# 72x8_control.net
KiCad netlist of a schematic drawn in EAGLE
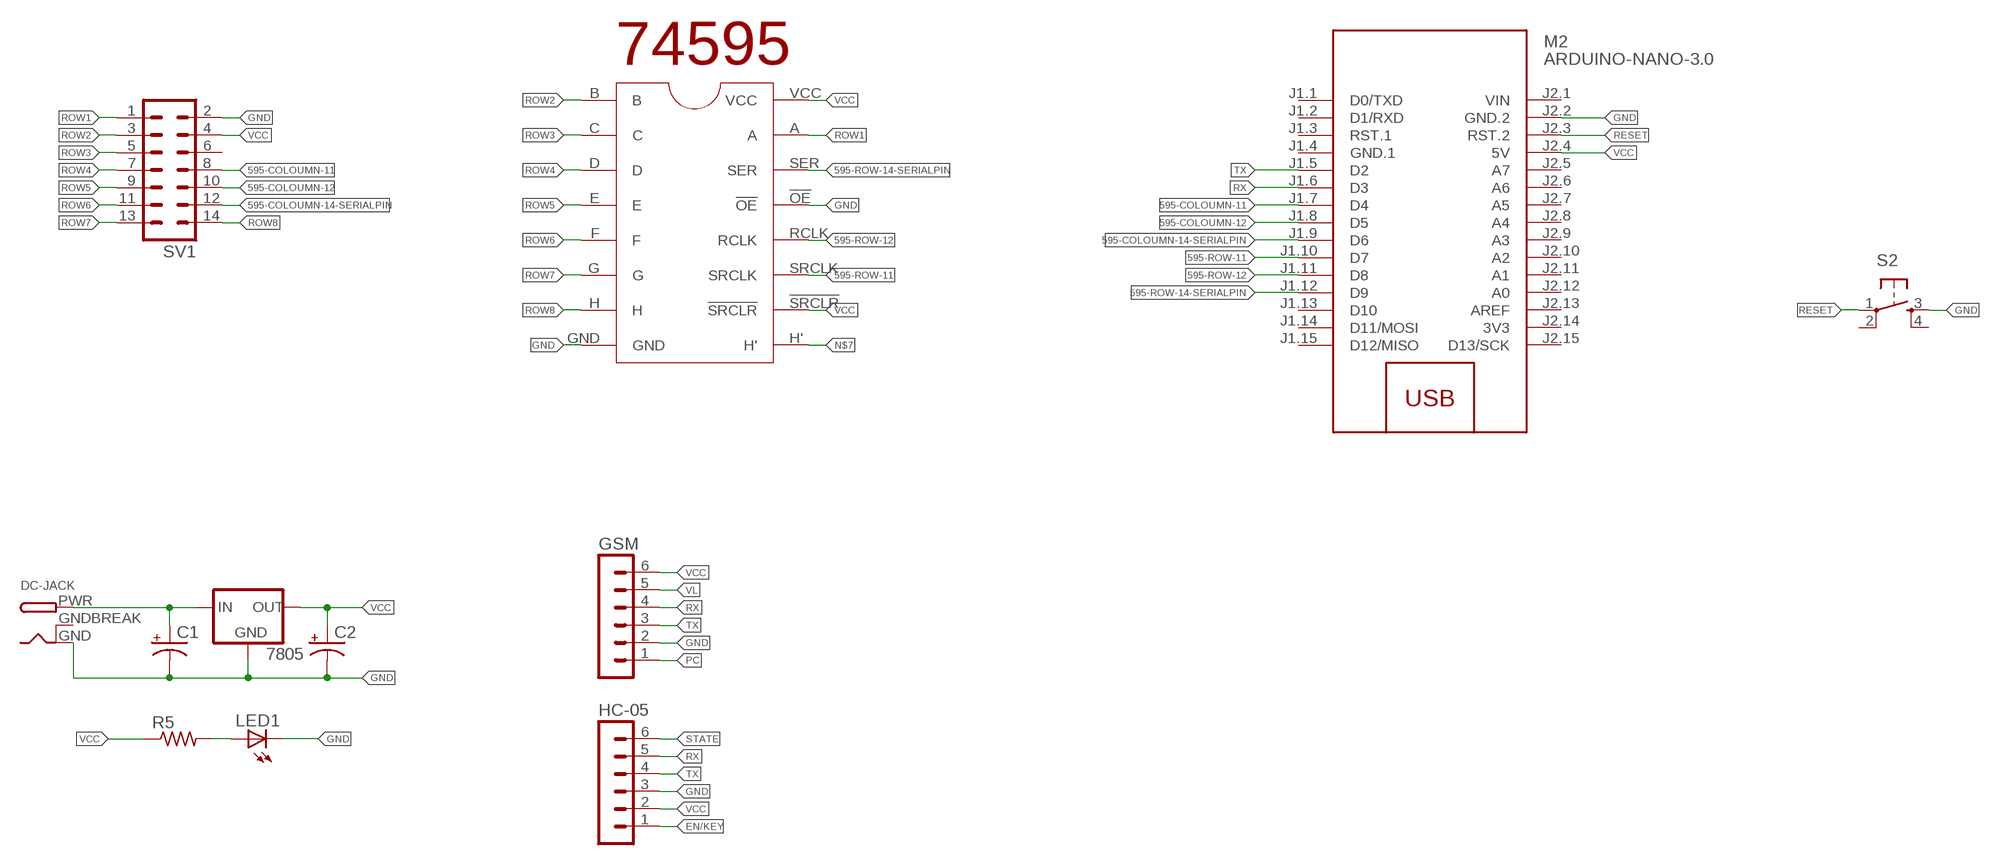
[diagram p0: schematic, sheet 1]

(export (version "E")
  (design (tool "Eeschema 10.0.6"))
  (components
    (comp (ref "1")
      (value "74595")
      (footprint "eagle-import:DIL16")
      (libsource (lib "eagle-import") (part "74595"))
    )
    (comp (ref "7805")
      (value "78XX-TO3")
      (footprint "eagle-import:TO3-78")
      (libsource (lib "eagle-import") (part "78XX-TO3"))
    )
    (comp (ref "C1")
      (value "CPOL-USE2-5")
      (footprint "eagle-import:E2-5")
      (libsource (lib "eagle-import") (part "CPOL-USE2-5"))
    )
    (comp (ref "C2")
      (value "CPOL-USE2-5")
      (footprint "eagle-import:E2-5")
      (libsource (lib "eagle-import") (part "CPOL-USE2-5"))
    )
    (comp (ref "DC-JACK")
      (value "DCBARRELPTH")
      (footprint "eagle-import:DCJACK_2MM_PTH")
      (libsource (lib "eagle-import") (part "DCBARRELPTH"))
    )
    (comp (ref "GSM")
      (value "MA06-1")
      (footprint "eagle-import:MA06-1")
      (libsource (lib "eagle-import") (part "MA06-1"))
    )
    (comp (ref "HC-05")
      (value "MA06-1")
      (footprint "eagle-import:MA06-1")
      (libsource (lib "eagle-import") (part "MA06-1"))
    )
    (comp (ref "LED1")
      (value "LED5MM")
      (footprint "eagle-import:LED5MM")
      (libsource (lib "eagle-import") (part "LED5MM"))
    )
    (comp (ref "M2")
      (value "ARDUINO-NANO-3.0")
      (footprint "eagle-import:ARDUINO-NANO-3.0")
      (libsource (lib "eagle-import") (part "ARDUINO-NANO-3.0"))
    )
    (comp (ref "R5")
      (value "R-US_0207/10")
      (footprint "eagle-import:0207_10")
      (libsource (lib "eagle-import") (part "R-US_0207/10"))
    )
    (comp (ref "S2")
      (value "TAC_SWITCHPTH")
      (footprint "eagle-import:TACTILE-PTH")
      (libsource (lib "eagle-import") (part "TAC_SWITCHPTH"))
    )
    (comp (ref "SV1")
      (value "MA07-2")
      (footprint "eagle-import:MA07-2")
      (libsource (lib "eagle-import") (part "MA07-2"))
    )
  )
  (nets
    (net (code "1") (name "/3V3") (class "Default")
      (node (ref "M2") (pin "J2.14") (pinfunction "3V3_J2.14") (pintype "power_in"))
    )
    (net (code "2") (name "/GND.1") (class "Default")
      (node (ref "M2") (pin "J1.4") (pinfunction "GND.1_J1.4") (pintype "power_in"))
    )
    (net (code "3") (name "/GNDBREAK") (class "Default")
      (node (ref "DC-JACK") (pin "GNDBREAK") (pinfunction "GNDBREAK_GNDBREAK") (pintype "power_in"))
    )
    (net (code "4") (name "/VIN") (class "Default")
      (node (ref "M2") (pin "J2.1") (pinfunction "VIN_J2.1") (pintype "power_in"))
    )
    (net (code "5") (name "595-COLOUMN-11") (class "Default")
      (node (ref "M2") (pin "J1.7") (pinfunction "D4_J1.7") (pintype "bidirectional"))
      (node (ref "SV1") (pin "8") (pinfunction "8_8") (pintype "passive"))
    )
    (net (code "6") (name "595-COLOUMN-12") (class "Default")
      (node (ref "M2") (pin "J1.8") (pinfunction "D5_J1.8") (pintype "bidirectional"))
      (node (ref "SV1") (pin "10") (pinfunction "10_10") (pintype "passive"))
    )
    (net (code "7") (name "595-COLOUMN-14-SERIALPIN") (class "Default")
      (node (ref "M2") (pin "J1.9") (pinfunction "D6_J1.9") (pintype "bidirectional"))
      (node (ref "SV1") (pin "12") (pinfunction "12_12") (pintype "passive"))
    )
    (net (code "8") (name "595-ROW-11") (class "Default")
      (node (ref "1") (pin "SRCLK") (pinfunction "SRCLK_SRCLK") (pintype "bidirectional"))
      (node (ref "M2") (pin "J1.10") (pinfunction "D7_J1.10") (pintype "bidirectional"))
    )
    (net (code "9") (name "595-ROW-12") (class "Default")
      (node (ref "1") (pin "RCLK") (pinfunction "RCLK_RCLK") (pintype "bidirectional"))
      (node (ref "M2") (pin "J1.11") (pinfunction "D8_J1.11") (pintype "bidirectional"))
    )
    (net (code "10") (name "595-ROW-14-SERIALPIN") (class "Default")
      (node (ref "1") (pin "SER") (pinfunction "SER_SER") (pintype "bidirectional"))
      (node (ref "M2") (pin "J1.12") (pinfunction "D9_J1.12") (pintype "bidirectional"))
    )
    (net (code "11") (name "EN{slash}KEY") (class "Default")
      (node (ref "HC-05") (pin "1") (pinfunction "1_1") (pintype "passive"))
    )
    (net (code "12") (name "GND") (class "Default")
      (node (ref "1") (pin "!OE") (pinfunction "~{OE}_!OE") (pintype "bidirectional"))
      (node (ref "1") (pin "GND") (pinfunction "GND_GND") (pintype "bidirectional"))
      (node (ref "7805") (pin "3") (pinfunction "GND_3") (pintype "input"))
      (node (ref "C1") (pin "-") (pinfunction "-_-") (pintype "passive"))
      (node (ref "C2") (pin "-") (pinfunction "-_-") (pintype "passive"))
      (node (ref "DC-JACK") (pin "GND") (pinfunction "GND_GND") (pintype "power_in"))
      (node (ref "GSM") (pin "2") (pinfunction "2_2") (pintype "passive"))
      (node (ref "HC-05") (pin "3") (pinfunction "3_3") (pintype "passive"))
      (node (ref "LED1") (pin "K") (pinfunction "C_K") (pintype "passive"))
      (node (ref "M2") (pin "J2.2") (pinfunction "GND.2_J2.2") (pintype "power_in"))
      (node (ref "S2") (pin "3") (pinfunction "3_3") (pintype "passive"))
      (node (ref "SV1") (pin "2") (pinfunction "2_2") (pintype "passive"))
    )
    (net (code "13") (name "N$7") (class "Default")
      (node (ref "1") (pin "H'") (pinfunction "H'_H'") (pintype "bidirectional"))
    )
    (net (code "14") (name "Net-(7805-IN)") (class "Default")
      (node (ref "7805") (pin "2") (pinfunction "IN_2") (pintype "input"))
      (node (ref "C1") (pin "+") (pinfunction "+_+") (pintype "passive"))
      (node (ref "DC-JACK") (pin "PWR") (pinfunction "PWR_PWR") (pintype "power_in"))
    )
    (net (code "15") (name "Net-(LED1-PadA)") (class "Default")
      (node (ref "LED1") (pin "A") (pinfunction "A_A") (pintype "passive"))
      (node (ref "R5") (pin "2") (pinfunction "2_2") (pintype "passive"))
    )
    (net (code "16") (name "PC") (class "Default")
      (node (ref "GSM") (pin "1") (pinfunction "1_1") (pintype "passive"))
    )
    (net (code "17") (name "RESET") (class "Default")
      (node (ref "M2") (pin "J2.3") (pinfunction "RST.2_J2.3") (pintype "bidirectional"))
      (node (ref "S2") (pin "1") (pinfunction "1_1") (pintype "passive"))
    )
    (net (code "18") (name "ROW1") (class "Default")
      (node (ref "1") (pin "A") (pinfunction "A_A") (pintype "bidirectional"))
      (node (ref "SV1") (pin "1") (pinfunction "1_1") (pintype "passive"))
    )
    (net (code "19") (name "ROW2") (class "Default")
      (node (ref "1") (pin "B") (pinfunction "B_B") (pintype "bidirectional"))
      (node (ref "SV1") (pin "3") (pinfunction "3_3") (pintype "passive"))
    )
    (net (code "20") (name "ROW3") (class "Default")
      (node (ref "1") (pin "C") (pinfunction "C_C") (pintype "bidirectional"))
      (node (ref "SV1") (pin "5") (pinfunction "5_5") (pintype "passive"))
    )
    (net (code "21") (name "ROW4") (class "Default")
      (node (ref "1") (pin "D") (pinfunction "D_D") (pintype "bidirectional"))
      (node (ref "SV1") (pin "7") (pinfunction "7_7") (pintype "passive"))
    )
    (net (code "22") (name "ROW5") (class "Default")
      (node (ref "1") (pin "E") (pinfunction "E_E") (pintype "bidirectional"))
      (node (ref "SV1") (pin "9") (pinfunction "9_9") (pintype "passive"))
    )
    (net (code "23") (name "ROW6") (class "Default")
      (node (ref "1") (pin "F") (pinfunction "F_F") (pintype "bidirectional"))
      (node (ref "SV1") (pin "11") (pinfunction "11_11") (pintype "passive"))
    )
    (net (code "24") (name "ROW7") (class "Default")
      (node (ref "1") (pin "G") (pinfunction "G_G") (pintype "bidirectional"))
      (node (ref "SV1") (pin "13") (pinfunction "13_13") (pintype "passive"))
    )
    (net (code "25") (name "ROW8") (class "Default")
      (node (ref "1") (pin "H") (pinfunction "H_H") (pintype "bidirectional"))
      (node (ref "SV1") (pin "14") (pinfunction "14_14") (pintype "passive"))
    )
    (net (code "26") (name "RX") (class "Default")
      (node (ref "GSM") (pin "4") (pinfunction "4_4") (pintype "passive"))
      (node (ref "HC-05") (pin "5") (pinfunction "5_5") (pintype "passive"))
      (node (ref "M2") (pin "J1.6") (pinfunction "D3_J1.6") (pintype "bidirectional"))
    )
    (net (code "27") (name "STATE") (class "Default")
      (node (ref "HC-05") (pin "6") (pinfunction "6_6") (pintype "passive"))
    )
    (net (code "28") (name "TX") (class "Default")
      (node (ref "GSM") (pin "3") (pinfunction "3_3") (pintype "passive"))
      (node (ref "HC-05") (pin "4") (pinfunction "4_4") (pintype "passive"))
      (node (ref "M2") (pin "J1.5") (pinfunction "D2_J1.5") (pintype "bidirectional"))
    )
    (net (code "29") (name "VCC") (class "Default")
      (node (ref "1") (pin "!SRCLR") (pinfunction "~{SRCLR}_!SRCLR") (pintype "bidirectional"))
      (node (ref "1") (pin "VCC") (pinfunction "VCC_VCC") (pintype "bidirectional"))
      (node (ref "7805") (pin "1") (pinfunction "OUT_1") (pintype "passive"))
      (node (ref "C2") (pin "+") (pinfunction "+_+") (pintype "passive"))
      (node (ref "GSM") (pin "6") (pinfunction "6_6") (pintype "passive"))
      (node (ref "HC-05") (pin "2") (pinfunction "2_2") (pintype "passive"))
      (node (ref "M2") (pin "J2.4") (pinfunction "5V_J2.4") (pintype "power_in"))
      (node (ref "R5") (pin "1") (pinfunction "1_1") (pintype "passive"))
      (node (ref "SV1") (pin "4") (pinfunction "4_4") (pintype "passive"))
    )
    (net (code "30") (name "VL") (class "Default")
      (node (ref "GSM") (pin "5") (pinfunction "5_5") (pintype "passive"))
    )
    (net (code "31") (name "unconnected-(M2-A0-PadJ2.12)") (class "Default")
      (node (ref "M2") (pin "J2.12") (pinfunction "A0_J2.12") (pintype "bidirectional"))
    )
    (net (code "32") (name "unconnected-(M2-A1-PadJ2.11)") (class "Default")
      (node (ref "M2") (pin "J2.11") (pinfunction "A1_J2.11") (pintype "bidirectional"))
    )
    (net (code "33") (name "unconnected-(M2-A2-PadJ2.10)") (class "Default")
      (node (ref "M2") (pin "J2.10") (pinfunction "A2_J2.10") (pintype "bidirectional"))
    )
    (net (code "34") (name "unconnected-(M2-A3-PadJ2.9)") (class "Default")
      (node (ref "M2") (pin "J2.9") (pinfunction "A3_J2.9") (pintype "bidirectional"))
    )
    (net (code "35") (name "unconnected-(M2-A4-PadJ2.8)") (class "Default")
      (node (ref "M2") (pin "J2.8") (pinfunction "A4_J2.8") (pintype "bidirectional"))
    )
    (net (code "36") (name "unconnected-(M2-A5-PadJ2.7)") (class "Default")
      (node (ref "M2") (pin "J2.7") (pinfunction "A5_J2.7") (pintype "bidirectional"))
    )
    (net (code "37") (name "unconnected-(M2-A6-PadJ2.6)") (class "Default")
      (node (ref "M2") (pin "J2.6") (pinfunction "A6_J2.6") (pintype "bidirectional"))
    )
    (net (code "38") (name "unconnected-(M2-A7-PadJ2.5)") (class "Default")
      (node (ref "M2") (pin "J2.5") (pinfunction "A7_J2.5") (pintype "bidirectional"))
    )
    (net (code "39") (name "unconnected-(M2-AREF-PadJ2.13)") (class "Default")
      (node (ref "M2") (pin "J2.13") (pinfunction "AREF_J2.13") (pintype "bidirectional"))
    )
    (net (code "40") (name "unconnected-(M2-D0{slash}TXD-PadJ1.1)") (class "Default")
      (node (ref "M2") (pin "J1.1") (pinfunction "D0/TXD_J1.1") (pintype "bidirectional"))
    )
    (net (code "41") (name "unconnected-(M2-D1{slash}RXD-PadJ1.2)") (class "Default")
      (node (ref "M2") (pin "J1.2") (pinfunction "D1/RXD_J1.2") (pintype "bidirectional"))
    )
    (net (code "42") (name "unconnected-(M2-D10-PadJ1.13)") (class "Default")
      (node (ref "M2") (pin "J1.13") (pinfunction "D10_J1.13") (pintype "bidirectional"))
    )
    (net (code "43") (name "unconnected-(M2-D11{slash}MOSI-PadJ1.14)") (class "Default")
      (node (ref "M2") (pin "J1.14") (pinfunction "D11/MOSI_J1.14") (pintype "bidirectional"))
    )
    (net (code "44") (name "unconnected-(M2-D12{slash}MISO-PadJ1.15)") (class "Default")
      (node (ref "M2") (pin "J1.15") (pinfunction "D12/MISO_J1.15") (pintype "bidirectional"))
    )
    (net (code "45") (name "unconnected-(M2-D13{slash}SCK-PadJ2.15)") (class "Default")
      (node (ref "M2") (pin "J2.15") (pinfunction "D13/SCK_J2.15") (pintype "bidirectional"))
    )
    (net (code "46") (name "unconnected-(M2-RST.1-PadJ1.3)") (class "Default")
      (node (ref "M2") (pin "J1.3") (pinfunction "RST.1_J1.3") (pintype "bidirectional"))
    )
    (net (code "47") (name "unconnected-(S2-Pad2)") (class "Default")
      (node (ref "S2") (pin "2") (pinfunction "2_2") (pintype "passive"))
    )
    (net (code "48") (name "unconnected-(S2-Pad4)") (class "Default")
      (node (ref "S2") (pin "4") (pinfunction "4_4") (pintype "passive"))
    )
    (net (code "49") (name "unconnected-(SV1-Pad6)") (class "Default")
      (node (ref "SV1") (pin "6") (pinfunction "6_6") (pintype "passive"))
    )
  )
)
